# mcu.net
KiCad netlist of a schematic drawn in Altium Designer
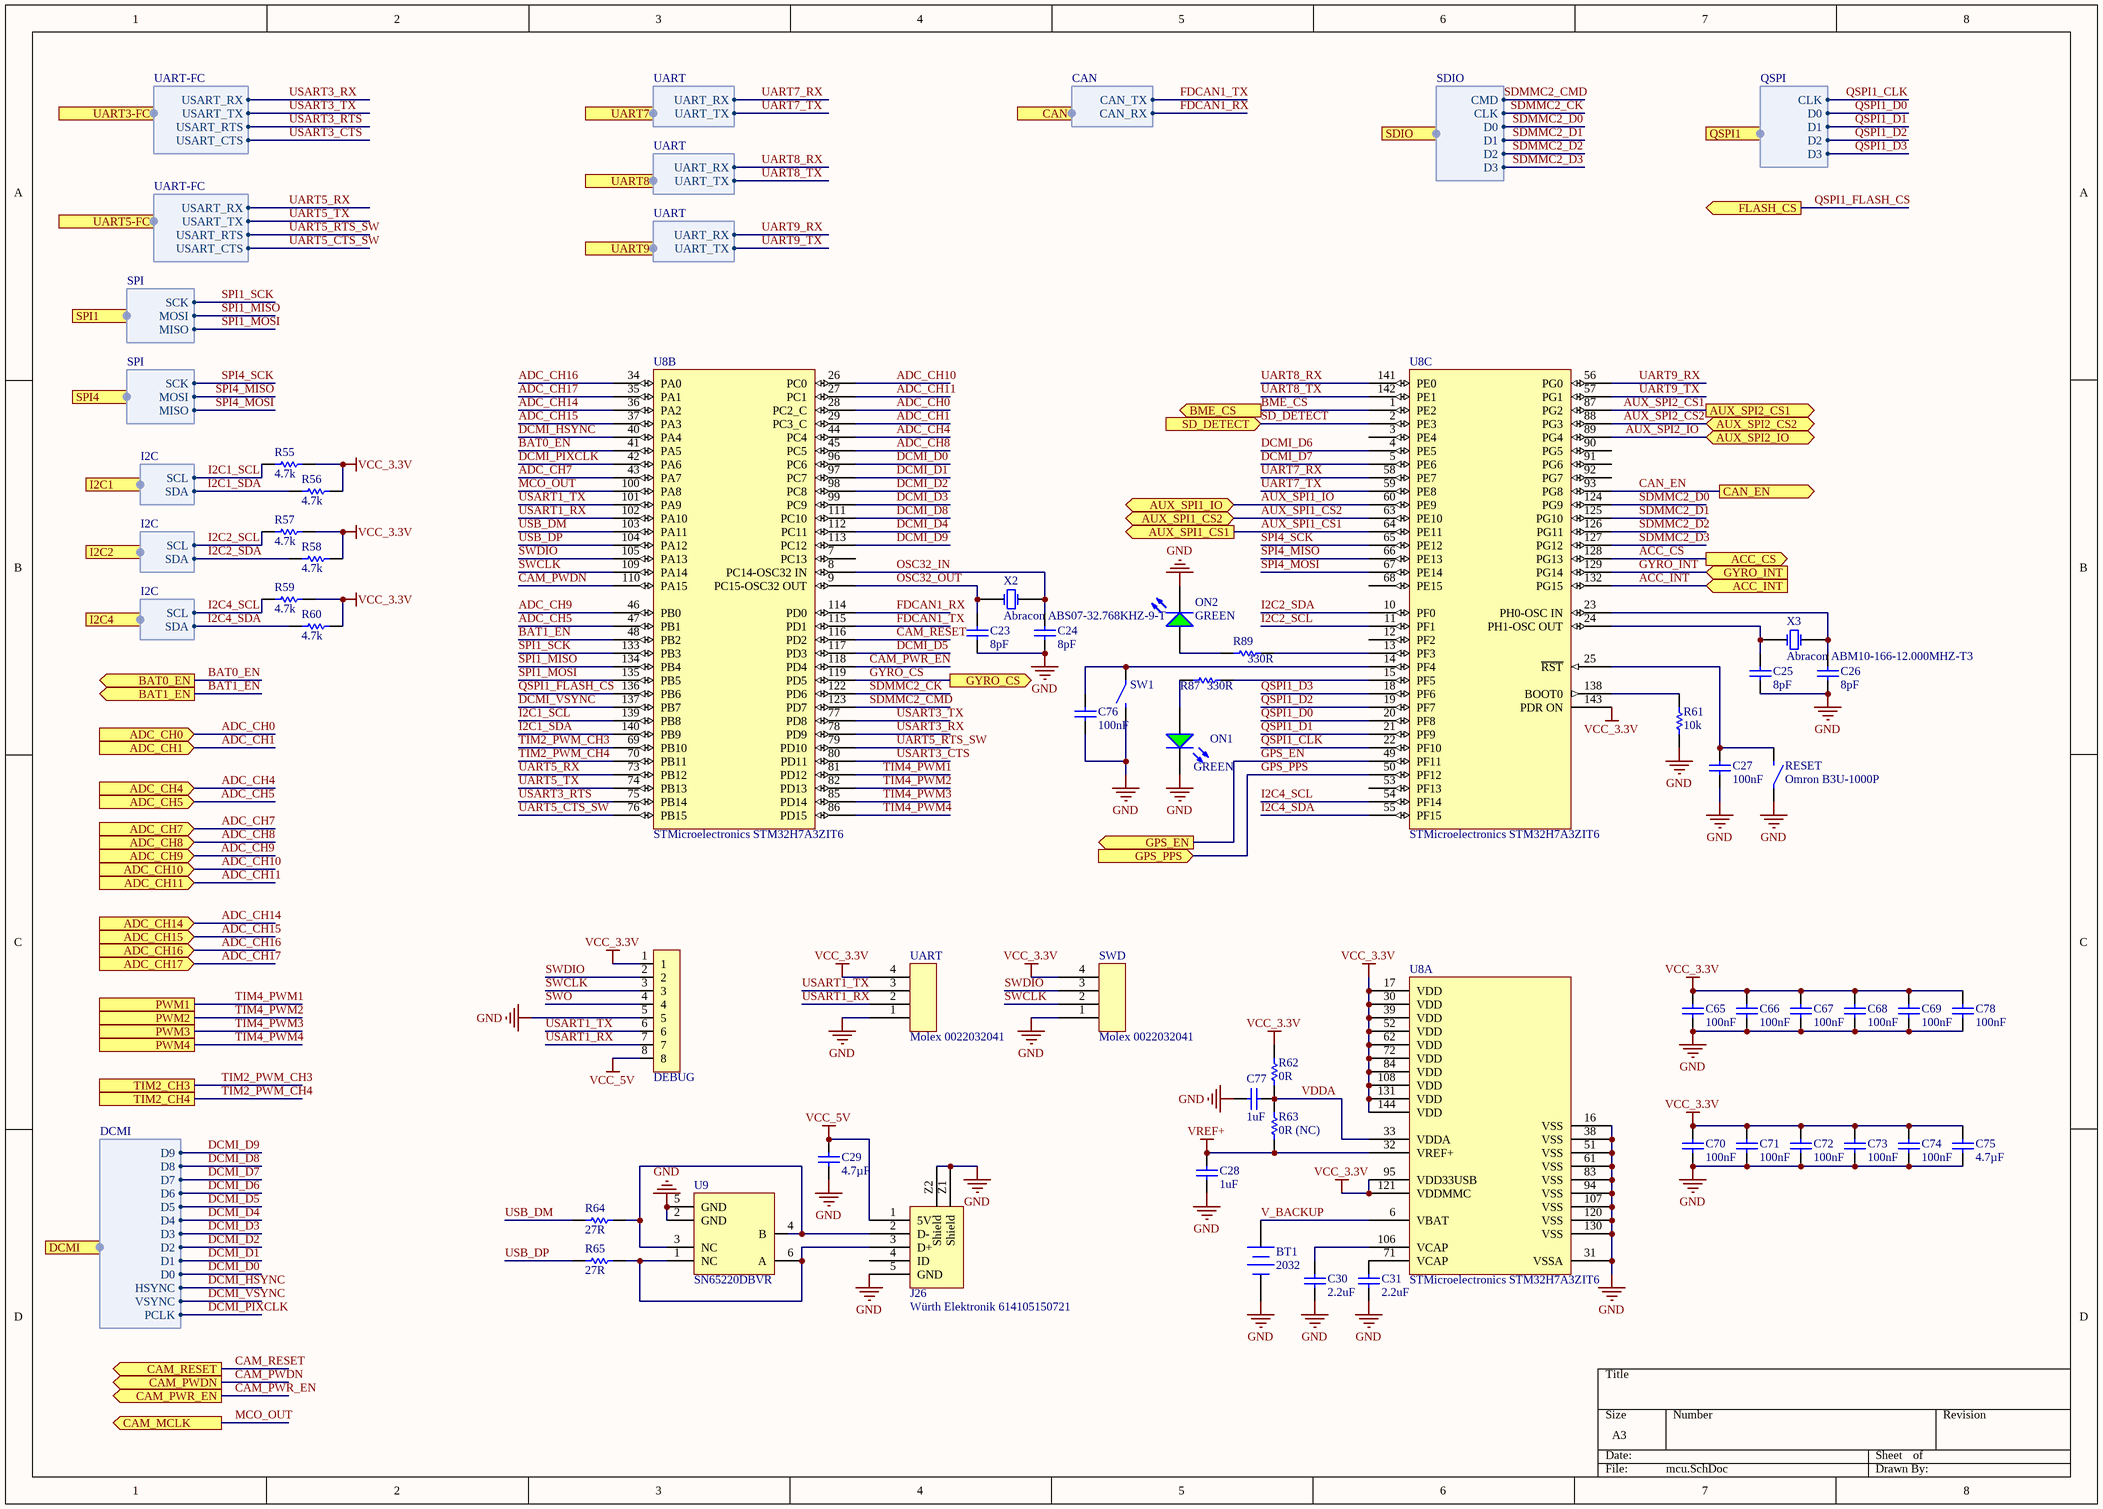
[diagram p0: mcu.SchDoc]

(export (version "E")
  (design (tool "Eeschema 10.0.6"))
  (components
    (comp (ref "BT1")
      (value "2032")
      (footprint "PCB-u4kor45r34oj4lfal23t-1")
      (description "Coin Cell Battery Holders 20MM (2032) SMT CELL HOLDER")
      (libsource (lib "CommunityVault") (part "SYM-19301741-1"))
    )
    (comp (ref "C23")
      (value "8pF")
      (footprint "CAPC1005X55X25NL05T10")
      (description "CAP CER 8PF 50V NP0 0402")
      (fields (field (name "MANUFACTURER PART NUMBER") "GJM1555C1H8R0WB01D"))
      (libsource (lib "CommunityVault") (part "CMP-137744-2"))
    )
    (comp (ref "C24")
      (value "8pF")
      (footprint "CAPC1005X55X25NL05T10")
      (description "CAP CER 8PF 50V NP0 0402")
      (fields (field (name "MANUFACTURER PART NUMBER") "GJM1555C1H8R0WB01D"))
      (libsource (lib "CommunityVault") (part "CMP-137744-2"))
    )
    (comp (ref "C25")
      (value "8pF")
      (footprint "CAPC1005X55X25NL05T10")
      (description "CAP CER 8PF 50V NP0 0402")
      (fields (field (name "MANUFACTURER PART NUMBER") "GJM1555C1H8R0WB01D"))
      (libsource (lib "CommunityVault") (part "CMP-137744-2"))
    )
    (comp (ref "C26")
      (value "8pF")
      (footprint "CAPC1005X55X25NL05T10")
      (description "CAP CER 8PF 50V NP0 0402")
      (fields (field (name "MANUFACTURER PART NUMBER") "GJM1555C1H8R0WB01D"))
      (libsource (lib "CommunityVault") (part "CMP-137744-2"))
    )
    (comp (ref "C27")
      (value "100nF")
      (footprint "CAPC1005X56X25NL10T15")
      (description "Ceramic capacitor SMD-0402 100nF /16V X7R# K +-10%, Samsung, RoHS")
      (libsource (lib "CommunityVault") (part "SYM-7bbdb0ed648ba47a-1"))
    )
    (comp (ref "C28")
      (value "1uF")
      (footprint "CAPC1005X60X30LL05T10")
      (description "Cap Ceramic 1uF 10V X5R 10% SMD 0402 85C Paper T/R")
      (fields (field (name "MANUFACTURER PART NUMBER") "C0402C105K8PACTU"))
      (libsource (lib "CommunityVault") (part "CMP-8752271-2"))
    )
    (comp (ref "C29")
      (value "4.7µF")
      (footprint "CAPC1608X90X35NL15T15")
      (description "0603 4.7 uF 10 V ±10 % Tolerance X5R SMT Multilayer Ceramic Capacitor")
      (libsource (lib "CommunityVault") (part "CAP-2"))
    )
    (comp (ref "C30")
      (value "2.2uF")
      (footprint "CAPC1005X56X25LL10T15")
      (description "AVX   04026D225KAT2A   CAP, MLCC, X5R, 2.2UF, 6.3V, 0402")
      (fields (field (name "MANUFACTURER PART NUMBER") "04026D225KAT2A"))
      (libsource (lib "CommunityVault") (part "CMP-954275-2"))
    )
    (comp (ref "C31")
      (value "2.2uF")
      (footprint "CAPC1005X56X25LL10T15")
      (description "AVX   04026D225KAT2A   CAP, MLCC, X5R, 2.2UF, 6.3V, 0402")
      (fields (field (name "MANUFACTURER PART NUMBER") "04026D225KAT2A"))
      (libsource (lib "CommunityVault") (part "CMP-954275-2"))
    )
    (comp (ref "C65")
      (value "100nF")
      (footprint "CAPC1005X56X25NL10T15")
      (description "Ceramic capacitor SMD-0402 100nF /16V X7R# K +-10%, Samsung, RoHS")
      (libsource (lib "CommunityVault") (part "SYM-7bbdb0ed648ba47a-1"))
    )
    (comp (ref "C66")
      (value "100nF")
      (footprint "CAPC1005X56X25NL10T15")
      (description "Ceramic capacitor SMD-0402 100nF /16V X7R# K +-10%, Samsung, RoHS")
      (libsource (lib "CommunityVault") (part "SYM-7bbdb0ed648ba47a-1"))
    )
    (comp (ref "C67")
      (value "100nF")
      (footprint "CAPC1005X56X25NL10T15")
      (description "Ceramic capacitor SMD-0402 100nF /16V X7R# K +-10%, Samsung, RoHS")
      (libsource (lib "CommunityVault") (part "SYM-7bbdb0ed648ba47a-1"))
    )
    (comp (ref "C68")
      (value "100nF")
      (footprint "CAPC1005X56X25NL10T15")
      (description "Ceramic capacitor SMD-0402 100nF /16V X7R# K +-10%, Samsung, RoHS")
      (libsource (lib "CommunityVault") (part "SYM-7bbdb0ed648ba47a-1"))
    )
    (comp (ref "C69")
      (value "100nF")
      (footprint "CAPC1005X56X25NL10T15")
      (description "Ceramic capacitor SMD-0402 100nF /16V X7R# K +-10%, Samsung, RoHS")
      (libsource (lib "CommunityVault") (part "SYM-7bbdb0ed648ba47a-1"))
    )
    (comp (ref "C70")
      (value "100nF")
      (footprint "CAPC1005X56X25NL10T15")
      (description "Ceramic capacitor SMD-0402 100nF /16V X7R# K +-10%, Samsung, RoHS")
      (libsource (lib "CommunityVault") (part "SYM-7bbdb0ed648ba47a-1"))
    )
    (comp (ref "C71")
      (value "100nF")
      (footprint "CAPC1005X56X25NL10T15")
      (description "Ceramic capacitor SMD-0402 100nF /16V X7R# K +-10%, Samsung, RoHS")
      (libsource (lib "CommunityVault") (part "SYM-7bbdb0ed648ba47a-1"))
    )
    (comp (ref "C72")
      (value "100nF")
      (footprint "CAPC1005X56X25NL10T15")
      (description "Ceramic capacitor SMD-0402 100nF /16V X7R# K +-10%, Samsung, RoHS")
      (libsource (lib "CommunityVault") (part "SYM-7bbdb0ed648ba47a-1"))
    )
    (comp (ref "C73")
      (value "100nF")
      (footprint "CAPC1005X56X25NL10T15")
      (description "Ceramic capacitor SMD-0402 100nF /16V X7R# K +-10%, Samsung, RoHS")
      (libsource (lib "CommunityVault") (part "SYM-7bbdb0ed648ba47a-1"))
    )
    (comp (ref "C74")
      (value "100nF")
      (footprint "CAPC1005X56X25NL10T15")
      (description "Ceramic capacitor SMD-0402 100nF /16V X7R# K +-10%, Samsung, RoHS")
      (libsource (lib "CommunityVault") (part "SYM-7bbdb0ed648ba47a-1"))
    )
    (comp (ref "C75")
      (value "4.7µF")
      (footprint "CAPC1608X90X35NL15T15")
      (description "0603 4.7 uF 10 V ±10 % Tolerance X5R SMT Multilayer Ceramic Capacitor")
      (libsource (lib "CommunityVault") (part "CAP-2"))
    )
    (comp (ref "C76")
      (value "100nF")
      (footprint "CAPC1005X56X25NL10T15")
      (description "Ceramic capacitor SMD-0402 100nF /16V X7R# K +-10%, Samsung, RoHS")
      (libsource (lib "CommunityVault") (part "SYM-7bbdb0ed648ba47a-1"))
    )
    (comp (ref "C77")
      (value "1uF")
      (footprint "CAPC1005X60X30LL05T10")
      (description "Cap Ceramic 1uF 10V X5R 10% SMD 0402 85C Paper T/R")
      (fields (field (name "MANUFACTURER PART NUMBER") "C0402C105K8PACTU"))
      (libsource (lib "CommunityVault") (part "CMP-8752271-2"))
    )
    (comp (ref "C78")
      (value "100nF")
      (footprint "CAPC1005X56X25NL10T15")
      (description "Ceramic capacitor SMD-0402 100nF /16V X7R# K +-10%, Samsung, RoHS")
      (libsource (lib "CommunityVault") (part "SYM-7bbdb0ed648ba47a-1"))
    )
    (comp (ref "DEBUG")
      (value "FCI HLW8R-2C7LF")
      (footprint "PCB-9fz4gdy3o615agpn7s9f-1")
      (description "FPC Connector; 0.5mm pitch dual contactback flip FPC; 8pos")
      (libsource (lib "CommunityVault") (part "SYM-1337d867f2d2ccf0-1"))
    )
    (comp (ref "J26")
      (value "Würth Elektronik 614105150721")
      (footprint "USB connector B")
      (description "Vertical Through Hole; Ver 2.0 Micro USB Connector Socket; 30 V ac; 1.8A WR-COM")
      (libsource (lib "CommunityVault") (part "SYM-1d65d74c74f4c2a2-1"))
    )
    (comp (ref "ON1")
      (value "GREEN")
      (footprint "LED-0603_D")
      (description "Super Ultra Green 0603 1.6 x 0.8 mm 140° Diffused 45 mcd 2.2 V PCB Chip SMT LED")
      (fields (field (name "MANUFACTURER PART NUMBER") "SML-LX0603SUGW-TR"))
      (libsource (lib "CommunityVault") (part "LED_GREEN_AC"))
    )
    (comp (ref "ON2")
      (value "GREEN")
      (footprint "LED-0603_D")
      (description "Super Ultra Green 0603 1.6 x 0.8 mm 140° Diffused 45 mcd 2.2 V PCB Chip SMT LED")
      (fields (field (name "MANUFACTURER PART NUMBER") "SML-LX0603SUGW-TR"))
      (libsource (lib "CommunityVault") (part "LED_GREEN_AC"))
    )
    (comp (ref "R55")
      (value "4.7k")
      (footprint "RESC1005X40X25NL10T10")
      (description "Thick Film Resistors - SMD 1/16watt 4.7Kohms 1%")
      (fields (field (name "MANUFACTURER PART NUMBER") "RK73H1ETTP4701F"))
      (libsource (lib "CommunityVault") (part "CMP-3660836-2"))
    )
    (comp (ref "R56")
      (value "4.7k")
      (footprint "RESC1005X40X25NL10T10")
      (description "Thick Film Resistors - SMD 1/16watt 4.7Kohms 1%")
      (fields (field (name "MANUFACTURER PART NUMBER") "RK73H1ETTP4701F"))
      (libsource (lib "CommunityVault") (part "CMP-3660836-2"))
    )
    (comp (ref "R57")
      (value "4.7k")
      (footprint "RESC1005X40X25NL10T10")
      (description "Thick Film Resistors - SMD 1/16watt 4.7Kohms 1%")
      (fields (field (name "MANUFACTURER PART NUMBER") "RK73H1ETTP4701F"))
      (libsource (lib "CommunityVault") (part "CMP-3660836-2"))
    )
    (comp (ref "R58")
      (value "4.7k")
      (footprint "RESC1005X40X25NL10T10")
      (description "Thick Film Resistors - SMD 1/16watt 4.7Kohms 1%")
      (fields (field (name "MANUFACTURER PART NUMBER") "RK73H1ETTP4701F"))
      (libsource (lib "CommunityVault") (part "CMP-3660836-2"))
    )
    (comp (ref "R59")
      (value "4.7k")
      (footprint "RESC1005X40X25NL10T10")
      (description "Thick Film Resistors - SMD 1/16watt 4.7Kohms 1%")
      (fields (field (name "MANUFACTURER PART NUMBER") "RK73H1ETTP4701F"))
      (libsource (lib "CommunityVault") (part "CMP-3660836-2"))
    )
    (comp (ref "R60")
      (value "4.7k")
      (footprint "RESC1005X40X25NL10T10")
      (description "Thick Film Resistors - SMD 1/16watt 4.7Kohms 1%")
      (fields (field (name "MANUFACTURER PART NUMBER") "RK73H1ETTP4701F"))
      (libsource (lib "CommunityVault") (part "CMP-3660836-2"))
    )
    (comp (ref "R61")
      (value "10k")
      (footprint "RESC1005X40X25NL05T10")
      (description "Thick Film Resistors - SMD 10K OHM 1%")
      (fields (field (name "MANUFACTURER PART NUMBER") "RC0402FR-1310KL"))
      (libsource (lib "CommunityVault") (part "CMP-3661304-2"))
    )
    (comp (ref "R62")
      (value "0R")
      (footprint "PCB-azzhouwj1h0sqqpj65ny-1")
      (description "RC Series 0402 0.063 W 0 Ohms Jumper Surface Mount Thick Film Chip Resistor")
      (libsource (lib "CommunityVault") (part "CMP-13527731-11"))
    )
    (comp (ref "R63")
      (value "0R (NC)")
      (footprint "PCB-azzhouwj1h0sqqpj65ny-1")
      (description "RC Series 0402 0.063 W 0 Ohms Jumper Surface Mount Thick Film Chip Resistor")
      (libsource (lib "CommunityVault") (part "CMP-13527731-11"))
    )
    (comp (ref "R64")
      (value "27R")
      (footprint "RESC1005X40X25NL05T05")
      (description "RES SMD 27 OHM 1% 1/16W 0402")
      (fields (field (name "MANUFACTURER PART NUMBER") "CRCW040227R0FKED"))
      (libsource (lib "CommunityVault") (part "CMP-3855807-2"))
    )
    (comp (ref "R65")
      (value "27R")
      (footprint "RESC1005X40X25NL05T05")
      (description "RES SMD 27 OHM 1% 1/16W 0402")
      (fields (field (name "MANUFACTURER PART NUMBER") "CRCW040227R0FKED"))
      (libsource (lib "CommunityVault") (part "CMP-3855807-2"))
    )
    (comp (ref "R87")
      (value "330R")
      (footprint "PCB-gqq469mmsoijq124jywu-1")
      (description "Res General Purpose Thick Film 0603 330 Ohm 5% 1/10W ±100ppm/°C Molded SMD Paper T/R")
      (fields (field (name "MANUFACTURER PART NUMBER") "RC0603JR-07330RL"))
      (libsource (lib "CommunityVault") (part "CMP-1852941-7"))
    )
    (comp (ref "R89")
      (value "330R")
      (footprint "PCB-gqq469mmsoijq124jywu-1")
      (description "Res General Purpose Thick Film 0603 330 Ohm 5% 1/10W ±100ppm/°C Molded SMD Paper T/R")
      (fields (field (name "MANUFACTURER PART NUMBER") "RC0603JR-07330RL"))
      (libsource (lib "CommunityVault") (part "CMP-1852941-7"))
    )
    (comp (ref "RESET")
      (value "Omron B3U-1000P")
      (footprint "PCB-a8ildroimidtkya2dspy-1")
      (description "Switch Tactile N.O. SPST Round Button Gull Wing 0.05A 12VDC 1.5N SMD Embossed T/R")
      (fields (field (name "MANUFACTURER PART NUMBER") "B3U-1000P"))
      (libsource (lib "FavoritesLibrary") (part "SYM-24bceda62397fb7b-1"))
    )
    (comp (ref "SW1")
      (value "Omron B3U-1000P")
      (footprint "PCB-a8ildroimidtkya2dspy-1")
      (description "Switch Tactile N.O. SPST Round Button Gull Wing 0.05A 12VDC 1.5N SMD Embossed T/R")
      (fields (field (name "MANUFACTURER PART NUMBER") "B3U-1000P"))
      (libsource (lib "FavoritesLibrary") (part "SYM-24bceda62397fb7b-1"))
    )
    (comp (ref "SWD")
      (value "Molex 0022032041")
      (footprint "PCB-w7fgx0p37qyww1etoafk-1")
      (description "Conn Unshrouded Header HDR 4 POS 2.54mm Solder ST Thru-Hole KK?? Bag")
      (libsource (lib "CommunityVault") (part "SYM-4df18464dcf59236-1"))
    )
    (comp (ref "U8")
      (value "STMicroelectronics STM32H7A3ZIT6")
      (footprint "PCB-qnuz4odb3kjwuv0h32wq-1")
      (description "STM32H Series 2 MB Flash 1.4 MB SRAM 280 MHz 32-Bit Microcontroller - LQFP-144")
      (fields (field (name "MANUFACTURER PART NUMBER") "STM32H7A3ZIT6"))
      (libsource (lib "FavoritesLibrary") (part "SYM-79c4b6aa4662a603-1"))
    )
    (comp (ref "U9")
      (value "SN65220DBVR")
      (footprint "DBV6_M")
      (libsource (lib "CommunityVault") (part "TI-SN65220-SOT-23_DBV-6"))
    )
    (comp (ref "UART")
      (value "Molex 0022032041")
      (footprint "PCB-w7fgx0p37qyww1etoafk-1")
      (description "Conn Unshrouded Header HDR 4 POS 2.54mm Solder ST Thru-Hole KK?? Bag")
      (libsource (lib "CommunityVault") (part "SYM-4df18464dcf59236-1"))
    )
    (comp (ref "X2")
      (value "Abracon ABS07-32.768KHZ-9-T")
      (footprint "CAPC3215X09N")
      (description "ABS07 Series 32.768 kHz ±20 ppm 9 pF -40 to +85 °C SMT Low Profile Crystal")
      (libsource (lib "CommunityVault") (part "SYM-ab256225872974e2-1"))
    )
    (comp (ref "X3")
      (value "Abracon ABM10-166-12.000MHZ-T3")
      (footprint "PCBComponent_1 - duplicate")
      (description "Crystal 12.00mhz 8pf Low Esr Smd 2.5x2.0")
      (libsource (lib "CommunityVault") (part "SYM-876f4e64f63d58a8-1"))
    )
  )
  (nets
    (net (code "9") (name "/ACC_CS") (class "Default")
      (node (ref "U8") (pin "128") (pinfunction "PG13_128") (pintype "bidirectional"))
    )
    (net (code "10") (name "/ACC_INT") (class "Default")
      (node (ref "U8") (pin "132") (pinfunction "PG15_132") (pintype "bidirectional"))
    )
    (net (code "11") (name "/ADC_CH0") (class "Default")
      (node (ref "U8") (pin "28") (pinfunction "PC2_C_28") (pintype "bidirectional"))
    )
    (net (code "12") (name "/ADC_CH1") (class "Default")
      (node (ref "U8") (pin "29") (pinfunction "PC3_C_29") (pintype "bidirectional"))
    )
    (net (code "13") (name "/ADC_CH4") (class "Default")
      (node (ref "U8") (pin "44") (pinfunction "PC4_44") (pintype "bidirectional"))
    )
    (net (code "14") (name "/ADC_CH5") (class "Default")
      (node (ref "U8") (pin "47") (pinfunction "PB1_47") (pintype "bidirectional"))
    )
    (net (code "15") (name "/ADC_CH7") (class "Default")
      (node (ref "U8") (pin "43") (pinfunction "PA7_43") (pintype "bidirectional"))
    )
    (net (code "16") (name "/ADC_CH8") (class "Default")
      (node (ref "U8") (pin "45") (pinfunction "PC5_45") (pintype "bidirectional"))
    )
    (net (code "17") (name "/ADC_CH9") (class "Default")
      (node (ref "U8") (pin "46") (pinfunction "PB0_46") (pintype "bidirectional"))
    )
    (net (code "18") (name "/ADC_CH10") (class "Default")
      (node (ref "U8") (pin "26") (pinfunction "PC0_26") (pintype "bidirectional"))
    )
    (net (code "19") (name "/ADC_CH11") (class "Default")
      (node (ref "U8") (pin "27") (pinfunction "PC1_27") (pintype "bidirectional"))
    )
    (net (code "20") (name "/ADC_CH14") (class "Default")
      (node (ref "U8") (pin "36") (pinfunction "PA2_36") (pintype "bidirectional"))
    )
    (net (code "21") (name "/ADC_CH15") (class "Default")
      (node (ref "U8") (pin "37") (pinfunction "PA3_37") (pintype "bidirectional"))
    )
    (net (code "22") (name "/ADC_CH16") (class "Default")
      (node (ref "U8") (pin "34") (pinfunction "PA0_34") (pintype "bidirectional"))
    )
    (net (code "23") (name "/ADC_CH17") (class "Default")
      (node (ref "U8") (pin "35") (pinfunction "PA1_35") (pintype "bidirectional"))
    )
    (net (code "24") (name "/AUX_SPI1_CS1") (class "Default")
      (node (ref "U8") (pin "64") (pinfunction "PE11_64") (pintype "bidirectional"))
    )
    (net (code "25") (name "/AUX_SPI1_CS2") (class "Default")
      (node (ref "U8") (pin "63") (pinfunction "PE10_63") (pintype "bidirectional"))
    )
    (net (code "26") (name "/AUX_SPI1_IO") (class "Default")
      (node (ref "U8") (pin "60") (pinfunction "PE9_60") (pintype "bidirectional"))
    )
    (net (code "27") (name "/AUX_SPI2_CS1") (class "Default")
      (node (ref "U8") (pin "87") (pinfunction "PG2_87") (pintype "bidirectional"))
    )
    (net (code "28") (name "/AUX_SPI2_CS2") (class "Default")
      (node (ref "U8") (pin "88") (pinfunction "PG3_88") (pintype "bidirectional"))
    )
    (net (code "29") (name "/AUX_SPI2_IO") (class "Default")
      (node (ref "U8") (pin "89") (pinfunction "PG4_89") (pintype "bidirectional"))
    )
    (net (code "30") (name "/BAT0_EN") (class "Default")
      (node (ref "U8") (pin "41") (pinfunction "PA5_41") (pintype "bidirectional"))
    )
    (net (code "31") (name "/BAT1_EN") (class "Default")
      (node (ref "U8") (pin "48") (pinfunction "PB2_48") (pintype "bidirectional"))
    )
    (net (code "32") (name "/BME_CS") (class "Default")
      (node (ref "U8") (pin "1") (pinfunction "PE2_1") (pintype "bidirectional"))
    )
    (net (code "33") (name "/CAM_PWDN") (class "Default")
      (node (ref "U8") (pin "110") (pinfunction "PA15_110") (pintype "bidirectional"))
    )
    (net (code "34") (name "/CAM_PWR_EN") (class "Default")
      (node (ref "U8") (pin "118") (pinfunction "PD4_118") (pintype "bidirectional"))
    )
    (net (code "35") (name "/CAM_RESET") (class "Default")
      (node (ref "U8") (pin "116") (pinfunction "PD2_116") (pintype "bidirectional"))
    )
    (net (code "36") (name "/CAN_EN") (class "Default")
      (node (ref "U8") (pin "93") (pinfunction "PG8_93") (pintype "bidirectional"))
    )
    (net (code "37") (name "/DCMI_D0") (class "Default")
      (node (ref "U8") (pin "96") (pinfunction "PC6_96") (pintype "bidirectional"))
    )
    (net (code "38") (name "/DCMI_D1") (class "Default")
      (node (ref "U8") (pin "97") (pinfunction "PC7_97") (pintype "bidirectional"))
    )
    (net (code "39") (name "/DCMI_D2") (class "Default")
      (node (ref "U8") (pin "98") (pinfunction "PC8_98") (pintype "bidirectional"))
    )
    (net (code "40") (name "/DCMI_D3") (class "Default")
      (node (ref "U8") (pin "99") (pinfunction "PC9_99") (pintype "bidirectional"))
    )
    (net (code "41") (name "/DCMI_D4") (class "Default")
      (node (ref "U8") (pin "112") (pinfunction "PC11_112") (pintype "bidirectional"))
    )
    (net (code "42") (name "/DCMI_D5") (class "Default")
      (node (ref "U8") (pin "117") (pinfunction "PD3_117") (pintype "bidirectional"))
    )
    (net (code "43") (name "/DCMI_D6") (class "Default")
      (node (ref "U8") (pin "4") (pinfunction "PE5_4") (pintype "bidirectional"))
    )
    (net (code "44") (name "/DCMI_D7") (class "Default")
      (node (ref "U8") (pin "5") (pinfunction "PE6_5") (pintype "bidirectional"))
    )
    (net (code "45") (name "/DCMI_D8") (class "Default")
      (node (ref "U8") (pin "111") (pinfunction "PC10_111") (pintype "bidirectional"))
    )
    (net (code "46") (name "/DCMI_D9") (class "Default")
      (node (ref "U8") (pin "113") (pinfunction "PC12_113") (pintype "bidirectional"))
    )
    (net (code "47") (name "/DCMI_HSYNC") (class "Default")
      (node (ref "U8") (pin "40") (pinfunction "PA4_40") (pintype "bidirectional"))
    )
    (net (code "48") (name "/DCMI_PIXCLK") (class "Default")
      (node (ref "U8") (pin "42") (pinfunction "PA6_42") (pintype "bidirectional"))
    )
    (net (code "49") (name "/DCMI_VSYNC") (class "Default")
      (node (ref "U8") (pin "137") (pinfunction "PB7_137") (pintype "bidirectional"))
    )
    (net (code "50") (name "/FDCAN1_RX") (class "Default")
      (node (ref "U8") (pin "114") (pinfunction "PD0_114") (pintype "bidirectional"))
    )
    (net (code "51") (name "/FDCAN1_TX") (class "Default")
      (node (ref "U8") (pin "115") (pinfunction "PD1_115") (pintype "bidirectional"))
    )
    (net (code "52") (name "/GPS_EN") (class "Default")
      (node (ref "U8") (pin "49") (pinfunction "PF11_49") (pintype "bidirectional"))
    )
    (net (code "53") (name "/GPS_PPS") (class "Default")
      (node (ref "U8") (pin "50") (pinfunction "PF12_50") (pintype "bidirectional"))
    )
    (net (code "54") (name "/GYRO_CS") (class "Default")
      (node (ref "U8") (pin "119") (pinfunction "PD5_119") (pintype "bidirectional"))
    )
    (net (code "55") (name "/GYRO_INT") (class "Default")
      (node (ref "U8") (pin "129") (pinfunction "PG14_129") (pintype "bidirectional"))
    )
    (net (code "56") (name "/I2C1_SCL") (class "Default")
      (node (ref "R55") (pin "1") (pinfunction "1_1") (pintype "passive"))
      (node (ref "U8") (pin "139") (pinfunction "PB8_139") (pintype "bidirectional"))
    )
    (net (code "57") (name "/I2C1_SDA") (class "Default")
      (node (ref "R56") (pin "1") (pinfunction "1_1") (pintype "passive"))
      (node (ref "U8") (pin "140") (pinfunction "PB9_140") (pintype "bidirectional"))
    )
    (net (code "58") (name "/I2C2_SCL") (class "Default")
      (node (ref "R57") (pin "1") (pinfunction "1_1") (pintype "passive"))
      (node (ref "U8") (pin "11") (pinfunction "PF1_11") (pintype "bidirectional"))
    )
    (net (code "59") (name "/I2C2_SDA") (class "Default")
      (node (ref "R58") (pin "1") (pinfunction "1_1") (pintype "passive"))
      (node (ref "U8") (pin "10") (pinfunction "PF0_10") (pintype "bidirectional"))
    )
    (net (code "60") (name "/I2C4_SCL") (class "Default")
      (node (ref "R59") (pin "1") (pinfunction "1_1") (pintype "passive"))
      (node (ref "U8") (pin "54") (pinfunction "PF14_54") (pintype "bidirectional"))
    )
    (net (code "61") (name "/I2C4_SDA") (class "Default")
      (node (ref "R60") (pin "1") (pinfunction "1_1") (pintype "passive"))
      (node (ref "U8") (pin "55") (pinfunction "PF15_55") (pintype "bidirectional"))
    )
    (net (code "62") (name "/MCO_OUT") (class "Default")
      (node (ref "U8") (pin "100") (pinfunction "PA8_100") (pintype "bidirectional"))
    )
    (net (code "63") (name "/OSC32_IN") (class "Default")
      (node (ref "C24") (pin "1") (pinfunction "1_1") (pintype "passive"))
      (node (ref "U8") (pin "8") (pinfunction "PC14-OSC32_IN_8") (pintype "bidirectional"))
      (node (ref "X2") (pin "2") (pinfunction "X2_2") (pintype "passive"))
    )
    (net (code "64") (name "/OSC32_OUT") (class "Default")
      (node (ref "C23") (pin "1") (pinfunction "1_1") (pintype "passive"))
      (node (ref "U8") (pin "9") (pinfunction "PC15-OSC32_OUT_9") (pintype "bidirectional"))
      (node (ref "X2") (pin "1") (pinfunction "X1_1") (pintype "passive"))
    )
    (net (code "65") (name "/QSPI1_CLK") (class "Default")
      (node (ref "U8") (pin "22") (pinfunction "PF10_22") (pintype "bidirectional"))
    )
    (net (code "66") (name "/QSPI1_D0") (class "Default")
      (node (ref "U8") (pin "20") (pinfunction "PF8_20") (pintype "bidirectional"))
    )
    (net (code "67") (name "/QSPI1_D1") (class "Default")
      (node (ref "U8") (pin "21") (pinfunction "PF9_21") (pintype "bidirectional"))
    )
    (net (code "68") (name "/QSPI1_D2") (class "Default")
      (node (ref "U8") (pin "19") (pinfunction "PF7_19") (pintype "bidirectional"))
    )
    (net (code "69") (name "/QSPI1_D3") (class "Default")
      (node (ref "U8") (pin "18") (pinfunction "PF6_18") (pintype "bidirectional"))
    )
    (net (code "70") (name "/QSPI1_FLASH_CS") (class "Default")
      (node (ref "U8") (pin "136") (pinfunction "PB6_136") (pintype "bidirectional"))
    )
    (net (code "71") (name "/SDMMC2_CK") (class "Default")
      (node (ref "U8") (pin "122") (pinfunction "PD6_122") (pintype "bidirectional"))
    )
    (net (code "72") (name "/SDMMC2_CMD") (class "Default")
      (node (ref "U8") (pin "123") (pinfunction "PD7_123") (pintype "bidirectional"))
    )
    (net (code "73") (name "/SDMMC2_D0") (class "Default")
      (node (ref "U8") (pin "124") (pinfunction "PG9_124") (pintype "bidirectional"))
    )
    (net (code "74") (name "/SDMMC2_D1") (class "Default")
      (node (ref "U8") (pin "125") (pinfunction "PG10_125") (pintype "bidirectional"))
    )
    (net (code "75") (name "/SDMMC2_D2") (class "Default")
      (node (ref "U8") (pin "126") (pinfunction "PG11_126") (pintype "bidirectional"))
    )
    (net (code "76") (name "/SDMMC2_D3") (class "Default")
      (node (ref "U8") (pin "127") (pinfunction "PG12_127") (pintype "bidirectional"))
    )
    (net (code "77") (name "/SD_DETECT") (class "Default")
      (node (ref "U8") (pin "2") (pinfunction "PE3_2") (pintype "bidirectional"))
    )
    (net (code "78") (name "/SPI1_MISO") (class "Default")
      (node (ref "U8") (pin "134") (pinfunction "PB4_134") (pintype "bidirectional"))
    )
    (net (code "79") (name "/SPI1_MOSI") (class "Default")
      (node (ref "U8") (pin "135") (pinfunction "PB5_135") (pintype "bidirectional"))
    )
    (net (code "80") (name "/SPI1_SCK") (class "Default")
      (node (ref "U8") (pin "133") (pinfunction "PB3_133") (pintype "bidirectional"))
    )
    (net (code "81") (name "/SPI4_MISO") (class "Default")
      (node (ref "U8") (pin "66") (pinfunction "PE13_66") (pintype "bidirectional"))
    )
    (net (code "82") (name "/SPI4_MOSI") (class "Default")
      (node (ref "U8") (pin "67") (pinfunction "PE14_67") (pintype "bidirectional"))
    )
    (net (code "83") (name "/SPI4_SCK") (class "Default")
      (node (ref "U8") (pin "65") (pinfunction "PE12_65") (pintype "bidirectional"))
    )
    (net (code "84") (name "/SWCLK") (class "Default")
      (node (ref "DEBUG") (pin "3") (pinfunction "3_3") (pintype "passive"))
      (node (ref "SWD") (pin "2") (pinfunction "1_2") (pintype "passive"))
      (node (ref "U8") (pin "109") (pinfunction "PA14_109") (pintype "bidirectional"))
    )
    (net (code "85") (name "/SWDIO") (class "Default")
      (node (ref "DEBUG") (pin "2") (pinfunction "2_2") (pintype "passive"))
      (node (ref "SWD") (pin "3") (pinfunction "1_3") (pintype "passive"))
      (node (ref "U8") (pin "105") (pinfunction "PA13_105") (pintype "bidirectional"))
    )
    (net (code "86") (name "/SWO") (class "Default")
      (node (ref "DEBUG") (pin "4") (pinfunction "4_4") (pintype "passive"))
    )
    (net (code "87") (name "/TIM2_PWM_CH3") (class "Default")
      (node (ref "U8") (pin "69") (pinfunction "PB10_69") (pintype "bidirectional"))
    )
    (net (code "88") (name "/TIM2_PWM_CH4") (class "Default")
      (node (ref "U8") (pin "70") (pinfunction "PB11_70") (pintype "bidirectional"))
    )
    (net (code "89") (name "/TIM4_PWM1") (class "Default")
      (node (ref "U8") (pin "81") (pinfunction "PD12_81") (pintype "bidirectional"))
    )
    (net (code "90") (name "/TIM4_PWM2") (class "Default")
      (node (ref "U8") (pin "82") (pinfunction "PD13_82") (pintype "bidirectional"))
    )
    (net (code "91") (name "/TIM4_PWM3") (class "Default")
      (node (ref "U8") (pin "85") (pinfunction "PD14_85") (pintype "bidirectional"))
    )
    (net (code "92") (name "/TIM4_PWM4") (class "Default")
      (node (ref "U8") (pin "86") (pinfunction "PD15_86") (pintype "bidirectional"))
    )
    (net (code "93") (name "/UART5_CTS_SW") (class "Default")
      (node (ref "U8") (pin "76") (pinfunction "PB15_76") (pintype "bidirectional"))
    )
    (net (code "94") (name "/UART5_RTS_SW") (class "Default")
      (node (ref "U8") (pin "79") (pinfunction "PD10_79") (pintype "bidirectional"))
    )
    (net (code "95") (name "/UART5_RX") (class "Default")
      (node (ref "U8") (pin "73") (pinfunction "PB12_73") (pintype "bidirectional"))
    )
    (net (code "96") (name "/UART5_TX") (class "Default")
      (node (ref "U8") (pin "74") (pinfunction "PB13_74") (pintype "bidirectional"))
    )
    (net (code "97") (name "/UART7_RX") (class "Default")
      (node (ref "U8") (pin "58") (pinfunction "PE7_58") (pintype "bidirectional"))
    )
    (net (code "98") (name "/UART7_TX") (class "Default")
      (node (ref "U8") (pin "59") (pinfunction "PE8_59") (pintype "bidirectional"))
    )
    (net (code "99") (name "/UART8_RX") (class "Default")
      (node (ref "U8") (pin "141") (pinfunction "PE0_141") (pintype "bidirectional"))
    )
    (net (code "100") (name "/UART8_TX") (class "Default")
      (node (ref "U8") (pin "142") (pinfunction "PE1_142") (pintype "bidirectional"))
    )
    (net (code "101") (name "/UART9_RX") (class "Default")
      (node (ref "U8") (pin "56") (pinfunction "PG0_56") (pintype "bidirectional"))
    )
    (net (code "102") (name "/UART9_TX") (class "Default")
      (node (ref "U8") (pin "57") (pinfunction "PG1_57") (pintype "bidirectional"))
    )
    (net (code "103") (name "/USART1_RX") (class "Default")
      (node (ref "DEBUG") (pin "7") (pinfunction "7_7") (pintype "passive"))
      (node (ref "U8") (pin "102") (pinfunction "PA10_102") (pintype "bidirectional"))
      (node (ref "UART") (pin "2") (pinfunction "1_2") (pintype "passive"))
    )
    (net (code "104") (name "/USART1_TX") (class "Default")
      (node (ref "DEBUG") (pin "6") (pinfunction "6_6") (pintype "passive"))
      (node (ref "U8") (pin "101") (pinfunction "PA9_101") (pintype "bidirectional"))
      (node (ref "UART") (pin "3") (pinfunction "1_3") (pintype "passive"))
    )
    (net (code "105") (name "/USART3_CTS") (class "Default")
      (node (ref "U8") (pin "80") (pinfunction "PD11_80") (pintype "bidirectional"))
    )
    (net (code "106") (name "/USART3_RTS") (class "Default")
      (node (ref "U8") (pin "75") (pinfunction "PB14_75") (pintype "bidirectional"))
    )
    (net (code "107") (name "/USART3_RX") (class "Default")
      (node (ref "U8") (pin "78") (pinfunction "PD9_78") (pintype "bidirectional"))
    )
    (net (code "108") (name "/USART3_TX") (class "Default")
      (node (ref "U8") (pin "77") (pinfunction "PD8_77") (pintype "bidirectional"))
    )
    (net (code "109") (name "/USB_DM") (class "Default")
      (node (ref "R64") (pin "1") (pinfunction "1_1") (pintype "passive"))
      (node (ref "U8") (pin "103") (pinfunction "PA11_103") (pintype "bidirectional"))
    )
    (net (code "110") (name "/USB_DP") (class "Default")
      (node (ref "R65") (pin "1") (pinfunction "1_1") (pintype "passive"))
      (node (ref "U8") (pin "104") (pinfunction "PA12_104") (pintype "bidirectional"))
    )
    (net (code "111") (name "/VDDA") (class "Default")
      (node (ref "C77") (pin "1") (pinfunction "1_1") (pintype "passive"))
      (node (ref "R62") (pin "1") (pinfunction "1_1") (pintype "passive"))
      (node (ref "R63") (pin "1") (pinfunction "1_1") (pintype "passive"))
      (node (ref "U8") (pin "33") (pinfunction "VDDA_33") (pintype "power_in"))
    )
    (net (code "112") (name "/V_BACKUP") (class "Default")
      (node (ref "BT1") (pin "1") (pinfunction "+_1") (pintype "passive"))
      (node (ref "U8") (pin "6") (pinfunction "VBAT_6") (pintype "power_in"))
    )
    (net (code "121") (name "GND") (class "Default")
      (node (ref "BT1") (pin "2") (pinfunction "-_2") (pintype "passive"))
      (node (ref "C23") (pin "2") (pinfunction "2_2") (pintype "passive"))
      (node (ref "C24") (pin "2") (pinfunction "2_2") (pintype "passive"))
      (node (ref "C25") (pin "2") (pinfunction "2_2") (pintype "passive"))
      (node (ref "C26") (pin "2") (pinfunction "2_2") (pintype "passive"))
      (node (ref "C27") (pin "1") (pinfunction "1_1") (pintype "passive"))
      (node (ref "C28") (pin "1") (pinfunction "1_1") (pintype "passive"))
      (node (ref "C29") (pin "2") (pinfunction "2_2") (pintype "passive"))
      (node (ref "C30") (pin "1") (pinfunction "1_1") (pintype "passive"))
      (node (ref "C31") (pin "1") (pinfunction "1_1") (pintype "passive"))
      (node (ref "C65") (pin "2") (pinfunction "2_2") (pintype "passive"))
      (node (ref "C66") (pin "2") (pinfunction "2_2") (pintype "passive"))
      (node (ref "C67") (pin "2") (pinfunction "2_2") (pintype "passive"))
      (node (ref "C68") (pin "2") (pinfunction "2_2") (pintype "passive"))
      (node (ref "C69") (pin "2") (pinfunction "2_2") (pintype "passive"))
      (node (ref "C70") (pin "2") (pinfunction "2_2") (pintype "passive"))
      (node (ref "C71") (pin "2") (pinfunction "2_2") (pintype "passive"))
      (node (ref "C72") (pin "2") (pinfunction "2_2") (pintype "passive"))
      (node (ref "C73") (pin "2") (pinfunction "2_2") (pintype "passive"))
      (node (ref "C74") (pin "2") (pinfunction "2_2") (pintype "passive"))
      (node (ref "C75") (pin "1") (pinfunction "1_1") (pintype "passive"))
      (node (ref "C76") (pin "1") (pinfunction "1_1") (pintype "passive"))
      (node (ref "C77") (pin "2") (pinfunction "2_2") (pintype "passive"))
      (node (ref "C78") (pin "2") (pinfunction "2_2") (pintype "passive"))
      (node (ref "DEBUG") (pin "5") (pinfunction "5_5") (pintype "passive"))
      (node (ref "J26") (pin "5") (pinfunction "GND_5") (pintype "passive"))
      (node (ref "J26") (pin "Z1") (pinfunction "Shield_Z1") (pintype "passive"))
      (node (ref "J26") (pin "Z2") (pinfunction "Shield_Z2") (pintype "passive"))
      (node (ref "ON1") (pin "C") (pinfunction "C_C") (pintype "passive"))
      (node (ref "ON2") (pin "C") (pinfunction "C_C") (pintype "passive"))
      (node (ref "R61") (pin "1") (pinfunction "1_1") (pintype "passive"))
      (node (ref "RESET") (pin "1") (pinfunction "1_1") (pintype "passive"))
      (node (ref "SW1") (pin "2") (pinfunction "2_2") (pintype "passive"))
      (node (ref "SWD") (pin "1") (pinfunction "1_1") (pintype "passive"))
      (node (ref "U8") (pin "107") (pinfunction "VSS_107") (pintype "power_in"))
      (node (ref "U8") (pin "120") (pinfunction "VSS_120") (pintype "power_in"))
      (node (ref "U8") (pin "130") (pinfunction "VSS_130") (pintype "power_in"))
      (node (ref "U8") (pin "16") (pinfunction "VSS_16") (pintype "power_in"))
      (node (ref "U8") (pin "31") (pinfunction "VSSA_31") (pintype "power_in"))
      (node (ref "U8") (pin "38") (pinfunction "VSS_38") (pintype "power_in"))
      (node (ref "U8") (pin "51") (pinfunction "VSS_51") (pintype "power_in"))
      (node (ref "U8") (pin "61") (pinfunction "VSS_61") (pintype "power_in"))
      (node (ref "U8") (pin "83") (pinfunction "VSS_83") (pintype "power_in"))
      (node (ref "U8") (pin "94") (pinfunction "VSS_94") (pintype "power_in"))
      (node (ref "U9") (pin "2") (pinfunction "GND_2") (pintype "power_in"))
      (node (ref "U9") (pin "5") (pinfunction "GND_5") (pintype "power_in"))
      (node (ref "UART") (pin "1") (pinfunction "1_1") (pintype "passive"))
    )
    (net (code "122") (name "Net-(C30-Pad2)") (class "Default")
      (node (ref "C30") (pin "2") (pinfunction "2_2") (pintype "passive"))
      (node (ref "U8") (pin "106") (pinfunction "VCAP_106") (pintype "power_in"))
    )
    (net (code "123") (name "Net-(C31-Pad2)") (class "Default")
      (node (ref "C31") (pin "2") (pinfunction "2_2") (pintype "passive"))
      (node (ref "U8") (pin "71") (pinfunction "VCAP_71") (pintype "power_in"))
    )
    (net (code "124") (name "Net-(J26-D+)") (class "Default")
      (node (ref "J26") (pin "3") (pinfunction "D+_3") (pintype "passive"))
      (node (ref "R65") (pin "2") (pinfunction "2_2") (pintype "passive"))
      (node (ref "U9") (pin "1") (pinfunction "NC_1") (pintype "passive"))
      (node (ref "U9") (pin "6") (pinfunction "A_6") (pintype "passive"))
    )
    (net (code "125") (name "Net-(J26-D-)") (class "Default")
      (node (ref "J26") (pin "2") (pinfunction "D-_2") (pintype "passive"))
      (node (ref "R64") (pin "2") (pinfunction "2_2") (pintype "passive"))
      (node (ref "U9") (pin "3") (pinfunction "NC_3") (pintype "passive"))
      (node (ref "U9") (pin "4") (pinfunction "B_4") (pintype "passive"))
    )
    (net (code "126") (name "Net-(ON1-PadA)") (class "Default")
      (node (ref "ON1") (pin "A") (pinfunction "A_A") (pintype "passive"))
      (node (ref "R87") (pin "2") (pinfunction "2_2") (pintype "passive"))
    )
    (net (code "127") (name "Net-(ON2-PadA)") (class "Default")
      (node (ref "ON2") (pin "A") (pinfunction "A_A") (pintype "passive"))
      (node (ref "R89") (pin "2") (pinfunction "2_2") (pintype "passive"))
    )
    (net (code "128") (name "Net-(U8C-BOOT0)") (class "Default")
      (node (ref "R61") (pin "2") (pinfunction "2_2") (pintype "passive"))
      (node (ref "U8") (pin "138") (pinfunction "BOOT0_138") (pintype "output"))
    )
    (net (code "129") (name "Net-(U8C-PF3)") (class "Default")
      (node (ref "R89") (pin "1") (pinfunction "1_1") (pintype "passive"))
      (node (ref "U8") (pin "13") (pinfunction "PF3_13") (pintype "bidirectional"))
    )
    (net (code "130") (name "Net-(U8C-PF4)") (class "Default")
      (node (ref "C76") (pin "2") (pinfunction "2_2") (pintype "passive"))
      (node (ref "SW1") (pin "1") (pinfunction "1_1") (pintype "passive"))
      (node (ref "U8") (pin "14") (pinfunction "PF4_14") (pintype "bidirectional"))
    )
    (net (code "131") (name "Net-(U8C-PF5)") (class "Default")
      (node (ref "R87") (pin "1") (pinfunction "1_1") (pintype "passive"))
      (node (ref "U8") (pin "15") (pinfunction "PF5_15") (pintype "bidirectional"))
    )
    (net (code "132") (name "Net-(U8C-PH0-OSC_IN)") (class "Default")
      (node (ref "C26") (pin "1") (pinfunction "1_1") (pintype "passive"))
      (node (ref "U8") (pin "23") (pinfunction "PH0-OSC_IN_23") (pintype "bidirectional"))
      (node (ref "X3") (pin "1") (pinfunction "X1_1") (pintype "passive"))
    )
    (net (code "133") (name "Net-(U8C-PH1-OSC_OUT)") (class "Default")
      (node (ref "C25") (pin "1") (pinfunction "1_1") (pintype "passive"))
      (node (ref "U8") (pin "24") (pinfunction "PH1-OSC_OUT_24") (pintype "bidirectional"))
      (node (ref "X3") (pin "3") (pinfunction "X2_3") (pintype "passive"))
    )
    (net (code "134") (name "Net-(U8C-~{RST})") (class "Default")
      (node (ref "C27") (pin "2") (pinfunction "2_2") (pintype "passive"))
      (node (ref "RESET") (pin "2") (pinfunction "2_2") (pintype "passive"))
      (node (ref "U8") (pin "25") (pinfunction "~{RST}_25") (pintype "input"))
    )
    (net (code "135") (name "VCC_3.3V") (class "Default")
      (node (ref "C65") (pin "1") (pinfunction "1_1") (pintype "passive"))
      (node (ref "C66") (pin "1") (pinfunction "1_1") (pintype "passive"))
      (node (ref "C67") (pin "1") (pinfunction "1_1") (pintype "passive"))
      (node (ref "C68") (pin "1") (pinfunction "1_1") (pintype "passive"))
      (node (ref "C69") (pin "1") (pinfunction "1_1") (pintype "passive"))
      (node (ref "C70") (pin "1") (pinfunction "1_1") (pintype "passive"))
      (node (ref "C71") (pin "1") (pinfunction "1_1") (pintype "passive"))
      (node (ref "C72") (pin "1") (pinfunction "1_1") (pintype "passive"))
      (node (ref "C73") (pin "1") (pinfunction "1_1") (pintype "passive"))
      (node (ref "C74") (pin "1") (pinfunction "1_1") (pintype "passive"))
      (node (ref "C75") (pin "2") (pinfunction "2_2") (pintype "passive"))
      (node (ref "C78") (pin "1") (pinfunction "1_1") (pintype "passive"))
      (node (ref "DEBUG") (pin "1") (pinfunction "1_1") (pintype "passive"))
      (node (ref "R55") (pin "2") (pinfunction "2_2") (pintype "passive"))
      (node (ref "R56") (pin "2") (pinfunction "2_2") (pintype "passive"))
      (node (ref "R57") (pin "2") (pinfunction "2_2") (pintype "passive"))
      (node (ref "R58") (pin "2") (pinfunction "2_2") (pintype "passive"))
      (node (ref "R59") (pin "2") (pinfunction "2_2") (pintype "passive"))
      (node (ref "R60") (pin "2") (pinfunction "2_2") (pintype "passive"))
      (node (ref "R62") (pin "2") (pinfunction "2_2") (pintype "passive"))
      (node (ref "SWD") (pin "4") (pinfunction "1_4") (pintype "passive"))
      (node (ref "U8") (pin "108") (pinfunction "VDD_108") (pintype "power_in"))
      (node (ref "U8") (pin "121") (pinfunction "VDDMMC_121") (pintype "power_in"))
      (node (ref "U8") (pin "131") (pinfunction "VDD_131") (pintype "power_in"))
      (node (ref "U8") (pin "143") (pinfunction "PDR_ON_143") (pintype "passive"))
      (node (ref "U8") (pin "144") (pinfunction "VDD_144") (pintype "power_in"))
      (node (ref "U8") (pin "17") (pinfunction "VDD_17") (pintype "power_in"))
      (node (ref "U8") (pin "30") (pinfunction "VDD_30") (pintype "power_in"))
      (node (ref "U8") (pin "39") (pinfunction "VDD_39") (pintype "power_in"))
      (node (ref "U8") (pin "52") (pinfunction "VDD_52") (pintype "power_in"))
      (node (ref "U8") (pin "62") (pinfunction "VDD_62") (pintype "power_in"))
      (node (ref "U8") (pin "72") (pinfunction "VDD_72") (pintype "power_in"))
      (node (ref "U8") (pin "84") (pinfunction "VDD_84") (pintype "power_in"))
      (node (ref "U8") (pin "95") (pinfunction "VDD33USB_95") (pintype "power_in"))
      (node (ref "UART") (pin "4") (pinfunction "1_4") (pintype "passive"))
    )
    (net (code "136") (name "VCC_5V") (class "Default")
      (node (ref "C29") (pin "1") (pinfunction "1_1") (pintype "passive"))
      (node (ref "DEBUG") (pin "8") (pinfunction "8_8") (pintype "passive"))
      (node (ref "J26") (pin "1") (pinfunction "5V_1") (pintype "passive"))
    )
    (net (code "137") (name "VREF+") (class "Default")
      (node (ref "C28") (pin "2") (pinfunction "2_2") (pintype "passive"))
      (node (ref "R63") (pin "2") (pinfunction "2_2") (pintype "passive"))
      (node (ref "U8") (pin "32") (pinfunction "VREF+_32") (pintype "power_in"))
    )
    (net (code "138") (name "unconnected-(J26-ID-Pad4)") (class "Default")
      (node (ref "J26") (pin "4") (pinfunction "ID_4") (pintype "passive"))
    )
    (net (code "139") (name "unconnected-(U8B-PC13-Pad7)") (class "Default")
      (node (ref "U8") (pin "7") (pinfunction "PC13_7") (pintype "bidirectional"))
    )
    (net (code "140") (name "unconnected-(U8C-PE4-Pad3)") (class "Default")
      (node (ref "U8") (pin "3") (pinfunction "PE4_3") (pintype "bidirectional"))
    )
    (net (code "141") (name "unconnected-(U8C-PE15-Pad68)") (class "Default")
      (node (ref "U8") (pin "68") (pinfunction "PE15_68") (pintype "bidirectional"))
    )
    (net (code "142") (name "unconnected-(U8C-PF2-Pad12)") (class "Default")
      (node (ref "U8") (pin "12") (pinfunction "PF2_12") (pintype "bidirectional"))
    )
    (net (code "143") (name "unconnected-(U8C-PF13-Pad53)") (class "Default")
      (node (ref "U8") (pin "53") (pinfunction "PF13_53") (pintype "bidirectional"))
    )
    (net (code "144") (name "unconnected-(U8C-PG5-Pad90)") (class "Default")
      (node (ref "U8") (pin "90") (pinfunction "PG5_90") (pintype "bidirectional"))
    )
    (net (code "145") (name "unconnected-(U8C-PG6-Pad91)") (class "Default")
      (node (ref "U8") (pin "91") (pinfunction "PG6_91") (pintype "bidirectional"))
    )
    (net (code "146") (name "unconnected-(U8C-PG7-Pad92)") (class "Default")
      (node (ref "U8") (pin "92") (pinfunction "PG7_92") (pintype "bidirectional"))
    )
  )
)
